# Emat.net
KiCad netlist of a schematic drawn in EAGLE
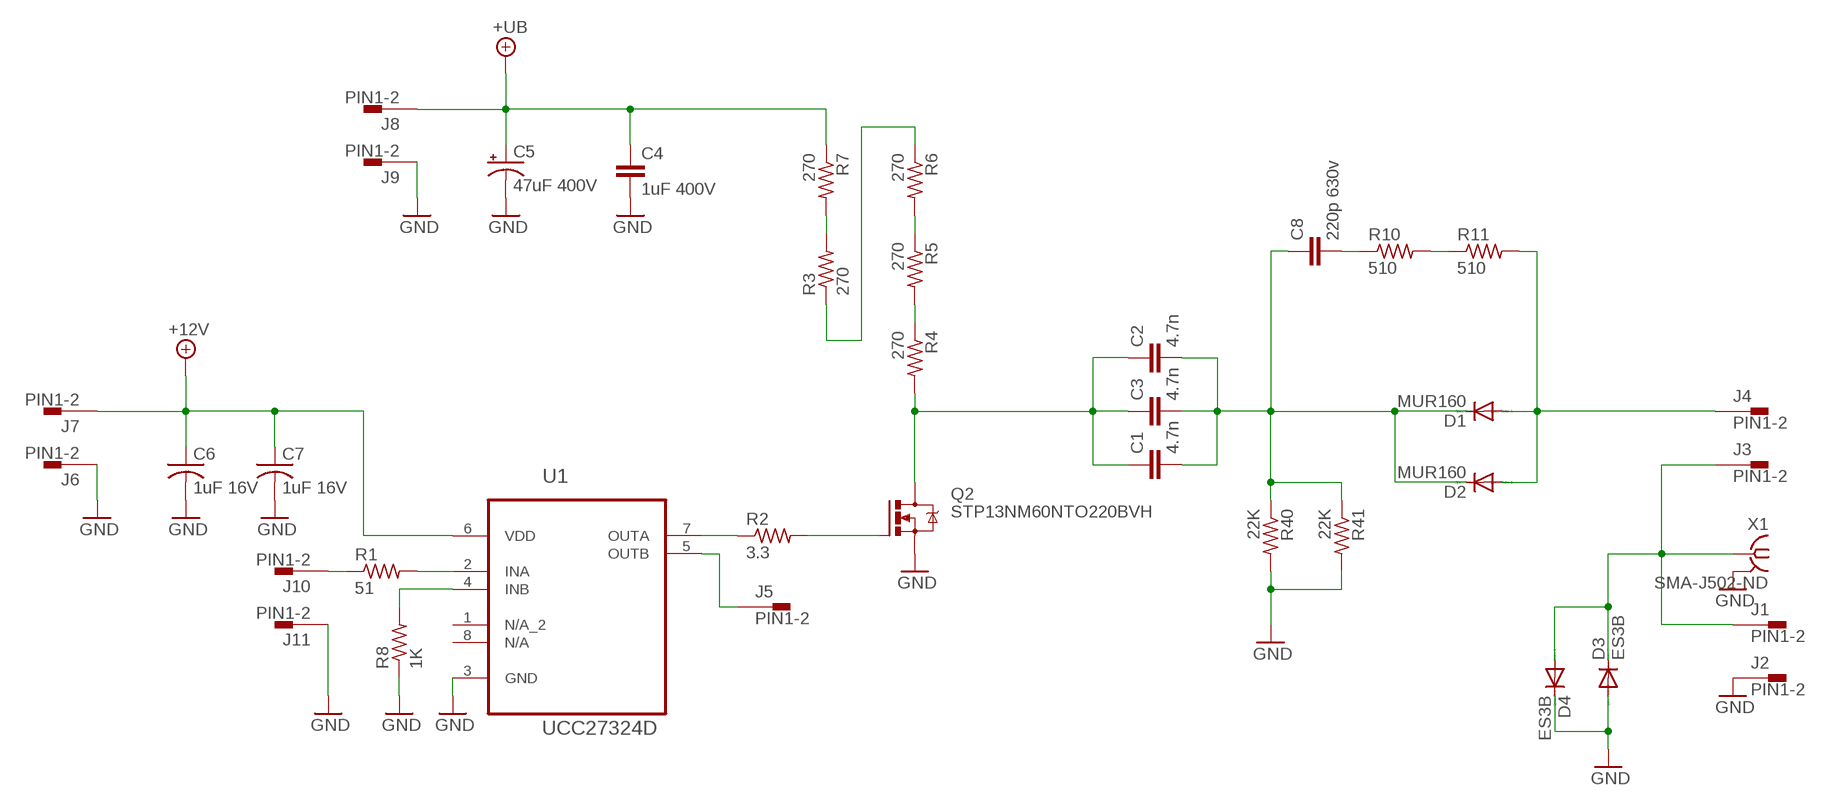
[diagram p0: schematic, sheet 1]

(export (version "E")
  (design (tool "Eeschema 10.0.6"))
  (components
    (comp (ref "C1")
      (value "4.7n")
      (footprint "eagle-import:C10B4")
      (libsource (lib "eagle-import") (part "C10/4"))
    )
    (comp (ref "C2")
      (value "4.7n")
      (footprint "eagle-import:C10B4")
      (libsource (lib "eagle-import") (part "C10/4"))
    )
    (comp (ref "C3")
      (value "4.7n")
      (footprint "eagle-import:C10B4")
      (libsource (lib "eagle-import") (part "C10/4"))
    )
    (comp (ref "C4")
      (value "1uF 400V")
      (footprint "eagle-import:C27.5B13")
      (libsource (lib "eagle-import") (part "C27/13"))
    )
    (comp (ref "C5")
      (value "47uF 400V")
      (footprint "eagle-import:SANYO-OSCON_G")
      (libsource (lib "eagle-import") (part "CPOL-USSANYO_G"))
    )
    (comp (ref "C6")
      (value "1uF 16V")
      (footprint "eagle-import:C0805")
      (libsource (lib "eagle-import") (part "C-USC0805"))
    )
    (comp (ref "C7")
      (value "1uF 16V")
      (footprint "eagle-import:C0805")
      (libsource (lib "eagle-import") (part "C-USC0805"))
    )
    (comp (ref "C8")
      (value "220p 630v")
      (footprint "eagle-import:C1206K")
      (libsource (lib "eagle-import") (part "C-EUC1206K"))
    )
    (comp (ref "D1")
      (value "MUR160")
      (footprint "eagle-import:DO41-10")
      (libsource (lib "eagle-import") (part "MUR160"))
    )
    (comp (ref "D2")
      (value "MUR160")
      (footprint "eagle-import:DO41-10")
      (libsource (lib "eagle-import") (part "MUR160"))
    )
    (comp (ref "D3")
      (value "ES3B")
      (footprint "eagle-import:SMC")
      (libsource (lib "eagle-import") (part "DIODE-SMC"))
    )
    (comp (ref "D4")
      (value "ES3B")
      (footprint "eagle-import:SMC")
      (libsource (lib "eagle-import") (part "DIODE-SMC"))
    )
    (comp (ref "J1")
      (value "PIN1-2")
      (footprint "eagle-import:62221")
      (fields (field (name "MF") "TYCO ELECTRONICS") (field (name "MPN") "62221-1"))
      (libsource (lib "eagle-import") (part "PIN1-2"))
    )
    (comp (ref "J2")
      (value "PIN1-2")
      (footprint "eagle-import:62221")
      (fields (field (name "MF") "TYCO ELECTRONICS") (field (name "MPN") "62221-1"))
      (libsource (lib "eagle-import") (part "PIN1-2"))
    )
    (comp (ref "J3")
      (value "PIN1-2")
      (footprint "eagle-import:62221")
      (fields (field (name "MF") "TYCO ELECTRONICS") (field (name "MPN") "62221-1"))
      (libsource (lib "eagle-import") (part "PIN1-2"))
    )
    (comp (ref "J4")
      (value "PIN1-2")
      (footprint "eagle-import:62221")
      (fields (field (name "MF") "TYCO ELECTRONICS") (field (name "MPN") "62221-1"))
      (libsource (lib "eagle-import") (part "PIN1-2"))
    )
    (comp (ref "J5")
      (value "PIN1-2")
      (footprint "eagle-import:62221")
      (fields (field (name "MF") "TYCO ELECTRONICS") (field (name "MPN") "62221-1"))
      (libsource (lib "eagle-import") (part "PIN1-2"))
    )
    (comp (ref "J6")
      (value "PIN1-2")
      (footprint "eagle-import:62221")
      (fields (field (name "MF") "TYCO ELECTRONICS") (field (name "MPN") "62221-1"))
      (libsource (lib "eagle-import") (part "PIN1-2"))
    )
    (comp (ref "J7")
      (value "PIN1-2")
      (footprint "eagle-import:62221")
      (fields (field (name "MF") "TYCO ELECTRONICS") (field (name "MPN") "62221-1"))
      (libsource (lib "eagle-import") (part "PIN1-2"))
    )
    (comp (ref "J8")
      (value "PIN1-2")
      (footprint "eagle-import:62221")
      (fields (field (name "MF") "TYCO ELECTRONICS") (field (name "MPN") "62221-1"))
      (libsource (lib "eagle-import") (part "PIN1-2"))
    )
    (comp (ref "J9")
      (value "PIN1-2")
      (footprint "eagle-import:62221")
      (fields (field (name "MF") "TYCO ELECTRONICS") (field (name "MPN") "62221-1"))
      (libsource (lib "eagle-import") (part "PIN1-2"))
    )
    (comp (ref "J10")
      (value "PIN1-2")
      (footprint "eagle-import:62221")
      (fields (field (name "MF") "TYCO ELECTRONICS") (field (name "MPN") "62221-1"))
      (libsource (lib "eagle-import") (part "PIN1-2"))
    )
    (comp (ref "J11")
      (value "PIN1-2")
      (footprint "eagle-import:62221")
      (fields (field (name "MF") "TYCO ELECTRONICS") (field (name "MPN") "62221-1"))
      (libsource (lib "eagle-import") (part "PIN1-2"))
    )
    (comp (ref "Q2")
      (value "STP13NM60NTO220BVH")
      (footprint "eagle-import:TO220BVH")
      (libsource (lib "eagle-import") (part "STP13NM60NTO220BVH"))
    )
    (comp (ref "R1")
      (value "51")
      (footprint "eagle-import:R1206")
      (libsource (lib "eagle-import") (part "R-US_R1206"))
    )
    (comp (ref "R2")
      (value "3.3")
      (footprint "eagle-import:R1206")
      (libsource (lib "eagle-import") (part "R-US_R1206"))
    )
    (comp (ref "R3")
      (value "270")
      (footprint "eagle-import:R2512")
      (libsource (lib "eagle-import") (part "resistor_R-US_R2512"))
    )
    (comp (ref "R4")
      (value "270")
      (footprint "eagle-import:R2512")
      (libsource (lib "eagle-import") (part "resistor_R-US_R2512"))
    )
    (comp (ref "R5")
      (value "270")
      (footprint "eagle-import:R2512")
      (libsource (lib "eagle-import") (part "resistor_R-US_R2512"))
    )
    (comp (ref "R6")
      (value "270")
      (footprint "eagle-import:R2512")
      (libsource (lib "eagle-import") (part "resistor_R-US_R2512"))
    )
    (comp (ref "R7")
      (value "270")
      (footprint "eagle-import:R2512")
      (libsource (lib "eagle-import") (part "resistor_R-US_R2512"))
    )
    (comp (ref "R8")
      (value "1K")
      (footprint "eagle-import:R1206")
      (libsource (lib "eagle-import") (part "R-US_R1206"))
    )
    (comp (ref "R10")
      (value "510")
      (footprint "eagle-import:R1206")
      (libsource (lib "eagle-import") (part "R-US_R1206"))
    )
    (comp (ref "R11")
      (value "510")
      (footprint "eagle-import:R1206")
      (libsource (lib "eagle-import") (part "R-US_R1206"))
    )
    (comp (ref "R40")
      (value "22K")
      (footprint "eagle-import:R2512")
      (libsource (lib "eagle-import") (part "R-US_R2512"))
    )
    (comp (ref "R41")
      (value "22K")
      (footprint "eagle-import:R2512")
      (libsource (lib "eagle-import") (part "R-US_R2512"))
    )
    (comp (ref "U1")
      (value "UCC27324D")
      (footprint "eagle-import:SOIC127P600X175-8N")
      (libsource (lib "eagle-import") (part "UCC27324D"))
    )
    (comp (ref "X1")
      (value "SMA-J502-ND")
      (footprint "eagle-import:J502-ND")
      (libsource (lib "eagle-import") (part "SMA-J502-ND"))
    )
  )
  (nets
    (net (code "1") (name "+12V") (class "Default")
      (node (ref "C6") (pin "1") (pinfunction "1_1") (pintype "passive"))
      (node (ref "C7") (pin "1") (pinfunction "1_1") (pintype "passive"))
      (node (ref "J7") (pin "1") (pinfunction "1_1") (pintype "passive"))
      (node (ref "U1") (pin "6") (pinfunction "VDD_6") (pintype "power_in"))
    )
    (net (code "2") (name "+UB") (class "Default")
      (node (ref "C4") (pin "1") (pinfunction "1_1") (pintype "passive"))
      (node (ref "C5") (pin "+") (pinfunction "+_+") (pintype "passive"))
      (node (ref "J8") (pin "1") (pinfunction "1_1") (pintype "passive"))
      (node (ref "R7") (pin "1") (pinfunction "1_1") (pintype "passive"))
    )
    (net (code "3") (name "GND") (class "Default")
      (node (ref "C4") (pin "2") (pinfunction "2_2") (pintype "passive"))
      (node (ref "C5") (pin "-") (pinfunction "-_-") (pintype "passive"))
      (node (ref "C6") (pin "2") (pinfunction "2_2") (pintype "passive"))
      (node (ref "C7") (pin "2") (pinfunction "2_2") (pintype "passive"))
      (node (ref "D3") (pin "A") (pinfunction "A_A") (pintype "passive"))
      (node (ref "D4") (pin "C") (pinfunction "C_C") (pintype "passive"))
      (node (ref "J11") (pin "1") (pinfunction "1_1") (pintype "passive"))
      (node (ref "J2") (pin "1") (pinfunction "1_1") (pintype "passive"))
      (node (ref "J6") (pin "1") (pinfunction "1_1") (pintype "passive"))
      (node (ref "J9") (pin "1") (pinfunction "1_1") (pintype "passive"))
      (node (ref "Q2") (pin "S") (pinfunction "S_S") (pintype "passive"))
      (node (ref "R40") (pin "2") (pinfunction "2_2") (pintype "passive"))
      (node (ref "R41") (pin "2") (pinfunction "2_2") (pintype "passive"))
      (node (ref "R8") (pin "1") (pinfunction "1_1") (pintype "passive"))
      (node (ref "U1") (pin "3") (pinfunction "GND_3") (pintype "passive"))
      (node (ref "X1") (pin "2") (pinfunction "2_2") (pintype "passive"))
      (node (ref "X1") (pin "3") (pinfunction "2_3") (pintype "passive"))
      (node (ref "X1") (pin "4") (pinfunction "2_4") (pintype "passive"))
      (node (ref "X1") (pin "5") (pinfunction "2_5") (pintype "passive"))
    )
    (net (code "4") (name "Net-(C1-Pad1)") (class "Default")
      (node (ref "C1") (pin "1") (pinfunction "1_1") (pintype "passive"))
      (node (ref "C2") (pin "1") (pinfunction "1_1") (pintype "passive"))
      (node (ref "C3") (pin "1") (pinfunction "1_1") (pintype "passive"))
      (node (ref "Q2") (pin "D") (pinfunction "D_D") (pintype "passive"))
      (node (ref "R4") (pin "2") (pinfunction "2_2") (pintype "passive"))
    )
    (net (code "5") (name "Net-(C1-Pad2)") (class "Default")
      (node (ref "C1") (pin "2") (pinfunction "2_2") (pintype "passive"))
      (node (ref "C2") (pin "2") (pinfunction "2_2") (pintype "passive"))
      (node (ref "C3") (pin "2") (pinfunction "2_2") (pintype "passive"))
      (node (ref "C8") (pin "1") (pinfunction "1_1") (pintype "passive"))
      (node (ref "D1") (pin "C") (pinfunction "C_C") (pintype "passive"))
      (node (ref "D2") (pin "C") (pinfunction "C_C") (pintype "passive"))
      (node (ref "R40") (pin "1") (pinfunction "1_1") (pintype "passive"))
      (node (ref "R41") (pin "1") (pinfunction "1_1") (pintype "passive"))
    )
    (net (code "6") (name "Net-(C8-Pad2)") (class "Default")
      (node (ref "C8") (pin "2") (pinfunction "2_2") (pintype "passive"))
      (node (ref "R10") (pin "1") (pinfunction "1_1") (pintype "passive"))
    )
    (net (code "7") (name "Net-(D1-PadA)") (class "Default")
      (node (ref "D1") (pin "A") (pinfunction "A_A") (pintype "passive"))
      (node (ref "D2") (pin "A") (pinfunction "A_A") (pintype "passive"))
      (node (ref "J4") (pin "1") (pinfunction "1_1") (pintype "passive"))
      (node (ref "R11") (pin "2") (pinfunction "2_2") (pintype "passive"))
    )
    (net (code "8") (name "Net-(D3-PadC)") (class "Default")
      (node (ref "D3") (pin "C") (pinfunction "C_C") (pintype "passive"))
      (node (ref "D4") (pin "A") (pinfunction "A_A") (pintype "passive"))
      (node (ref "J1") (pin "1") (pinfunction "1_1") (pintype "passive"))
      (node (ref "J3") (pin "1") (pinfunction "1_1") (pintype "passive"))
      (node (ref "X1") (pin "1") (pinfunction "1_1") (pintype "passive"))
    )
    (net (code "9") (name "Net-(J10-Pad1)") (class "Default")
      (node (ref "J10") (pin "1") (pinfunction "1_1") (pintype "passive"))
      (node (ref "R1") (pin "1") (pinfunction "1_1") (pintype "passive"))
    )
    (net (code "10") (name "Net-(Q2-PadG)") (class "Default")
      (node (ref "Q2") (pin "G") (pinfunction "G_G") (pintype "passive"))
      (node (ref "R2") (pin "2") (pinfunction "2_2") (pintype "passive"))
    )
    (net (code "11") (name "Net-(R3-Pad1)") (class "Default")
      (node (ref "R3") (pin "1") (pinfunction "1_1") (pintype "passive"))
      (node (ref "R6") (pin "1") (pinfunction "1_1") (pintype "passive"))
    )
    (net (code "12") (name "Net-(R3-Pad2)") (class "Default")
      (node (ref "R3") (pin "2") (pinfunction "2_2") (pintype "passive"))
      (node (ref "R7") (pin "2") (pinfunction "2_2") (pintype "passive"))
    )
    (net (code "13") (name "Net-(R4-Pad1)") (class "Default")
      (node (ref "R4") (pin "1") (pinfunction "1_1") (pintype "passive"))
      (node (ref "R5") (pin "2") (pinfunction "2_2") (pintype "passive"))
    )
    (net (code "14") (name "Net-(R5-Pad1)") (class "Default")
      (node (ref "R5") (pin "1") (pinfunction "1_1") (pintype "passive"))
      (node (ref "R6") (pin "2") (pinfunction "2_2") (pintype "passive"))
    )
    (net (code "15") (name "Net-(R10-Pad2)") (class "Default")
      (node (ref "R10") (pin "2") (pinfunction "2_2") (pintype "passive"))
      (node (ref "R11") (pin "1") (pinfunction "1_1") (pintype "passive"))
    )
    (net (code "16") (name "Net-(U1-INA)") (class "Default")
      (node (ref "R1") (pin "2") (pinfunction "2_2") (pintype "passive"))
      (node (ref "U1") (pin "2") (pinfunction "INA_2") (pintype "input"))
    )
    (net (code "17") (name "Net-(U1-INB)") (class "Default")
      (node (ref "R8") (pin "2") (pinfunction "2_2") (pintype "passive"))
      (node (ref "U1") (pin "4") (pinfunction "INB_4") (pintype "input"))
    )
    (net (code "18") (name "Net-(U1-OUTA)") (class "Default")
      (node (ref "R2") (pin "1") (pinfunction "1_1") (pintype "passive"))
      (node (ref "U1") (pin "7") (pinfunction "OUTA_7") (pintype "output"))
    )
    (net (code "19") (name "Net-(U1-OUTB)") (class "Default")
      (node (ref "J5") (pin "1") (pinfunction "1_1") (pintype "passive"))
      (node (ref "U1") (pin "5") (pinfunction "OUTB_5") (pintype "output"))
    )
    (net (code "20") (name "unconnected-(U1-N{slash}A-Pad8)") (class "Default")
      (node (ref "U1") (pin "8") (pinfunction "N/A_8") (pintype "no_connect"))
    )
    (net (code "21") (name "unconnected-(U1-N{slash}A_2-Pad1)") (class "Default")
      (node (ref "U1") (pin "1") (pinfunction "N/A_2_1") (pintype "no_connect"))
    )
  )
)
